# mattduino_leonardo.net
KiCad netlist of a schematic drawn in EAGLE
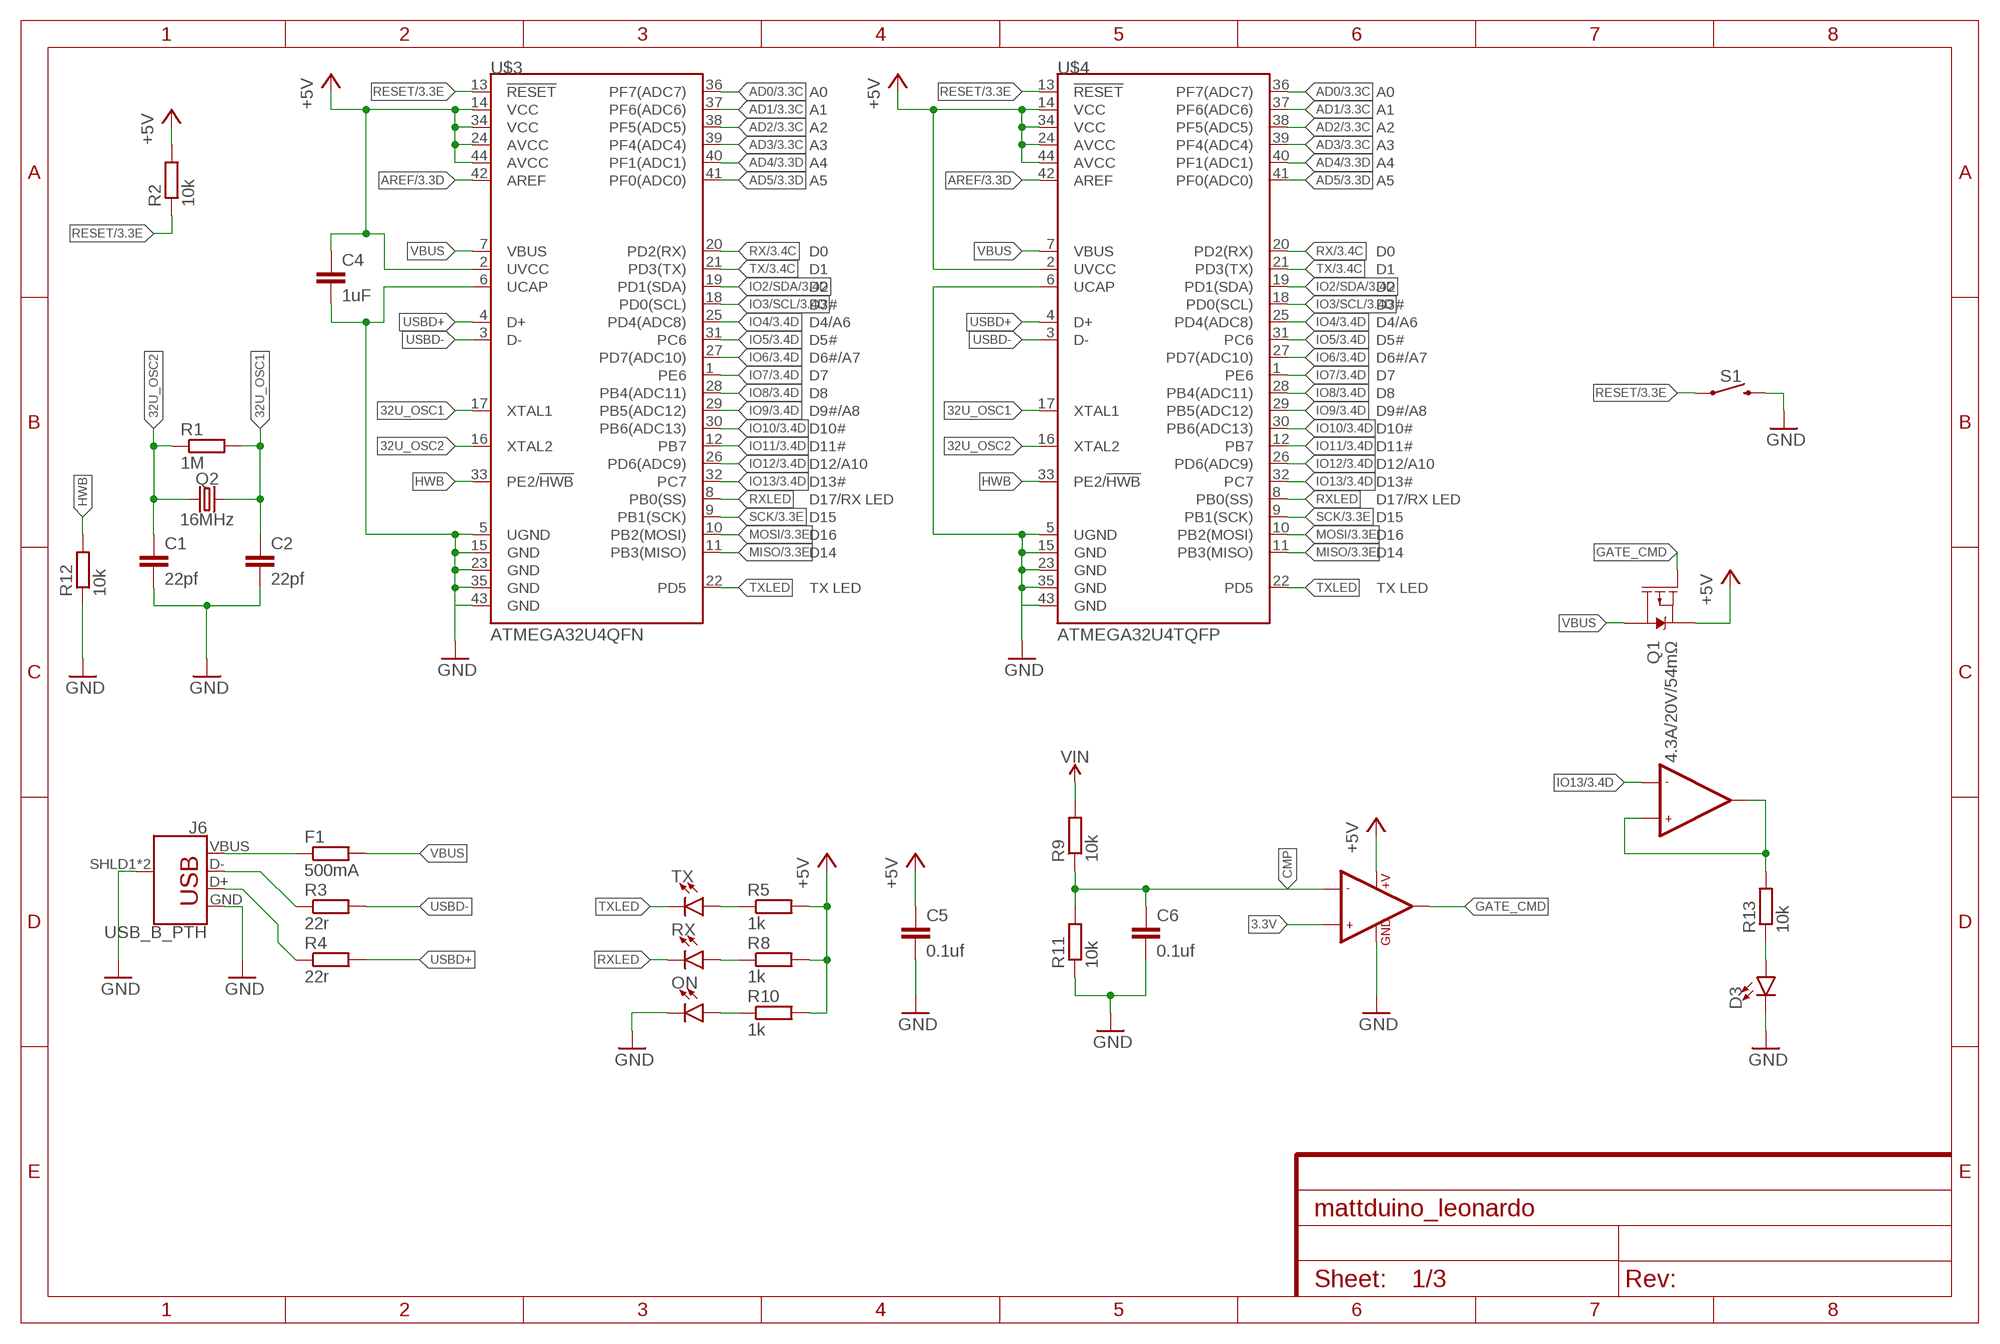
[diagram p0: schematic, sheet 1]
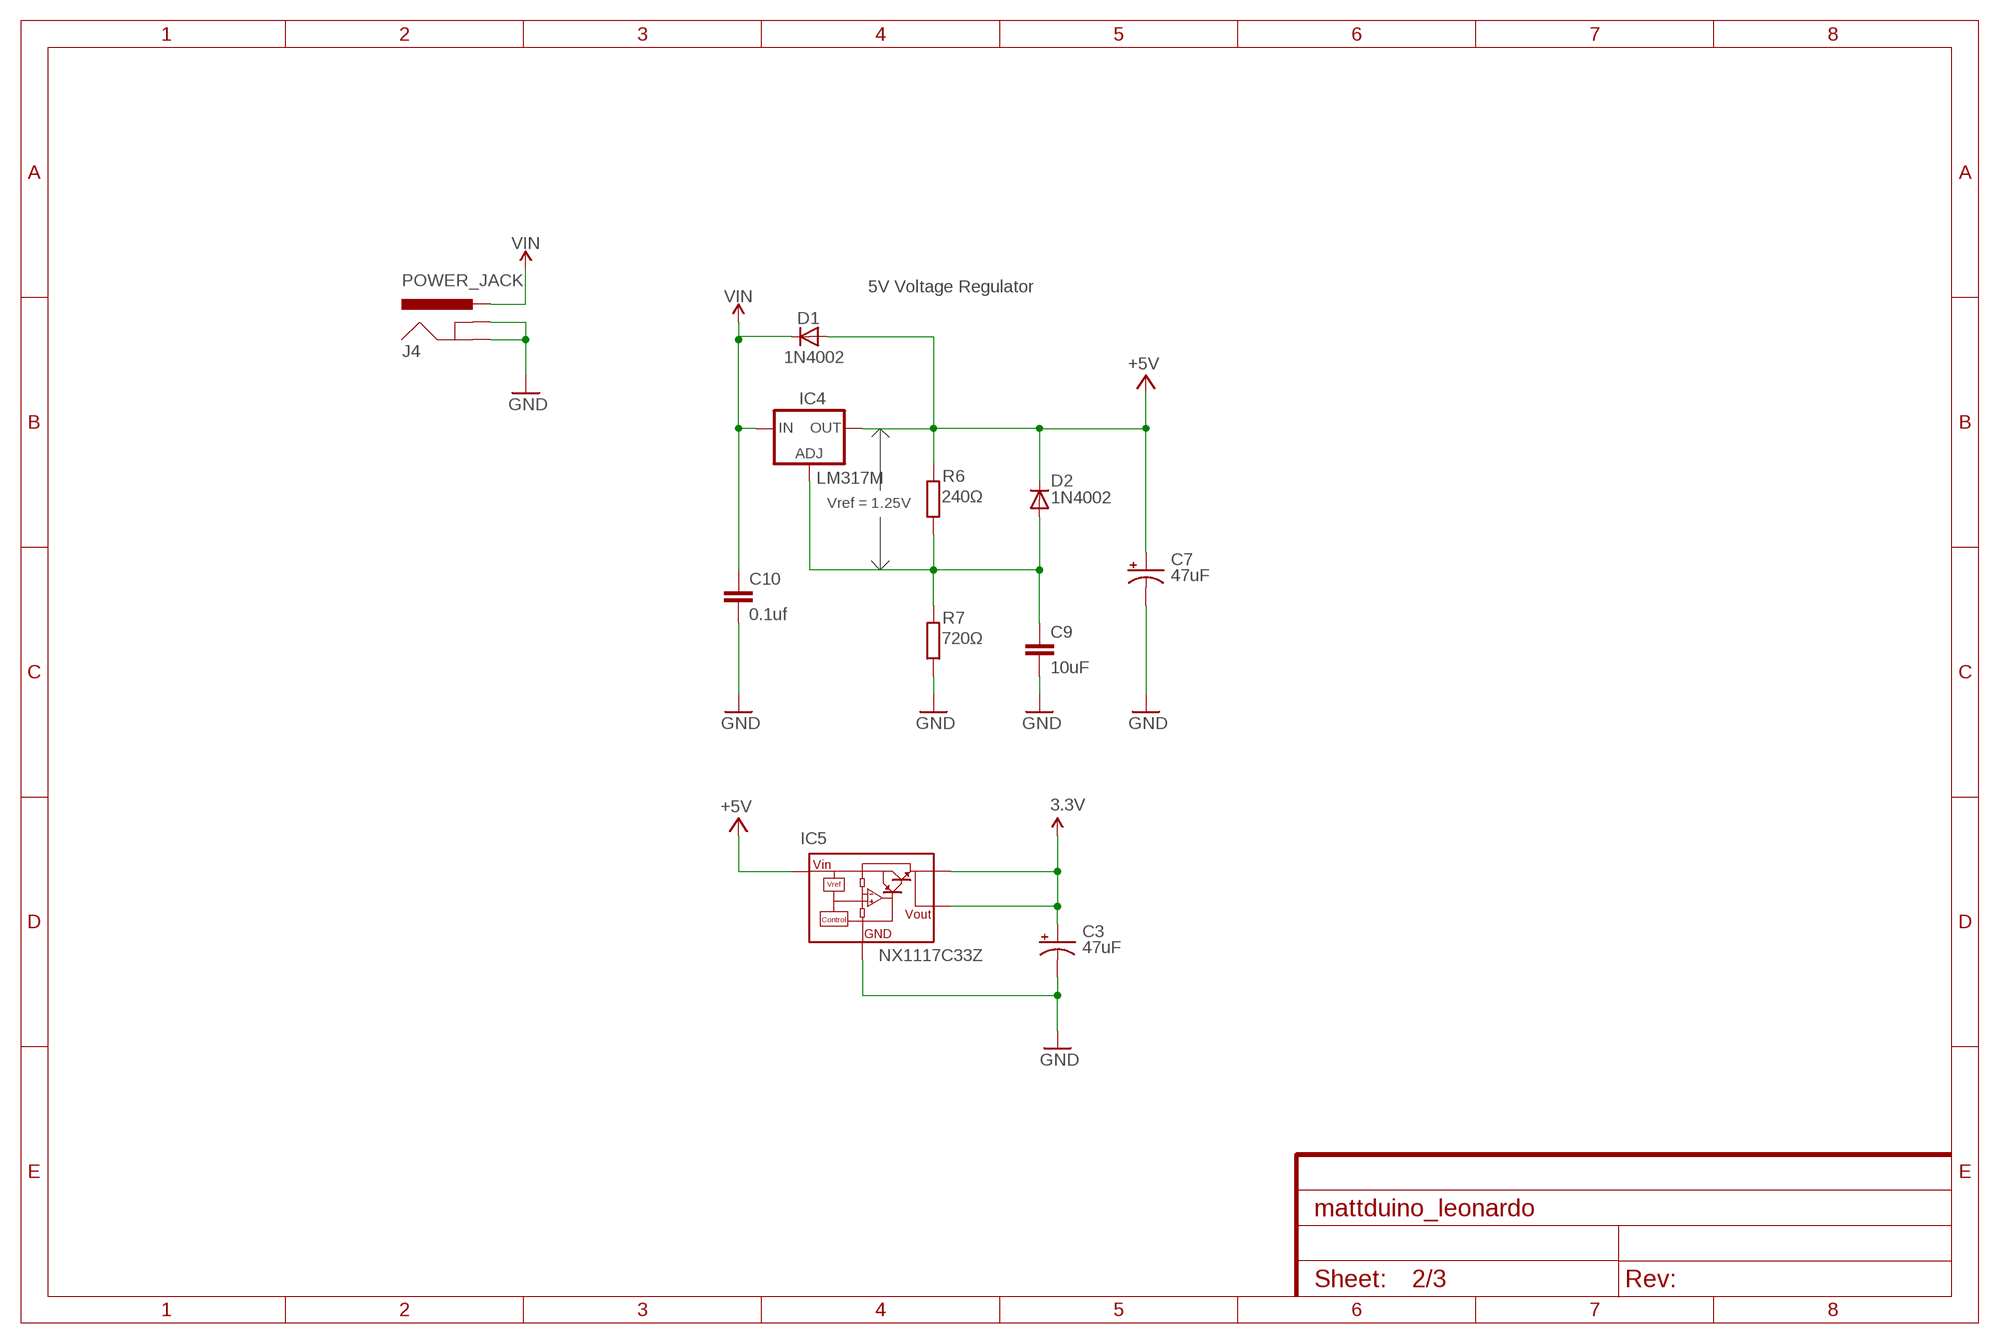
[diagram p1: schematic, sheet 2]
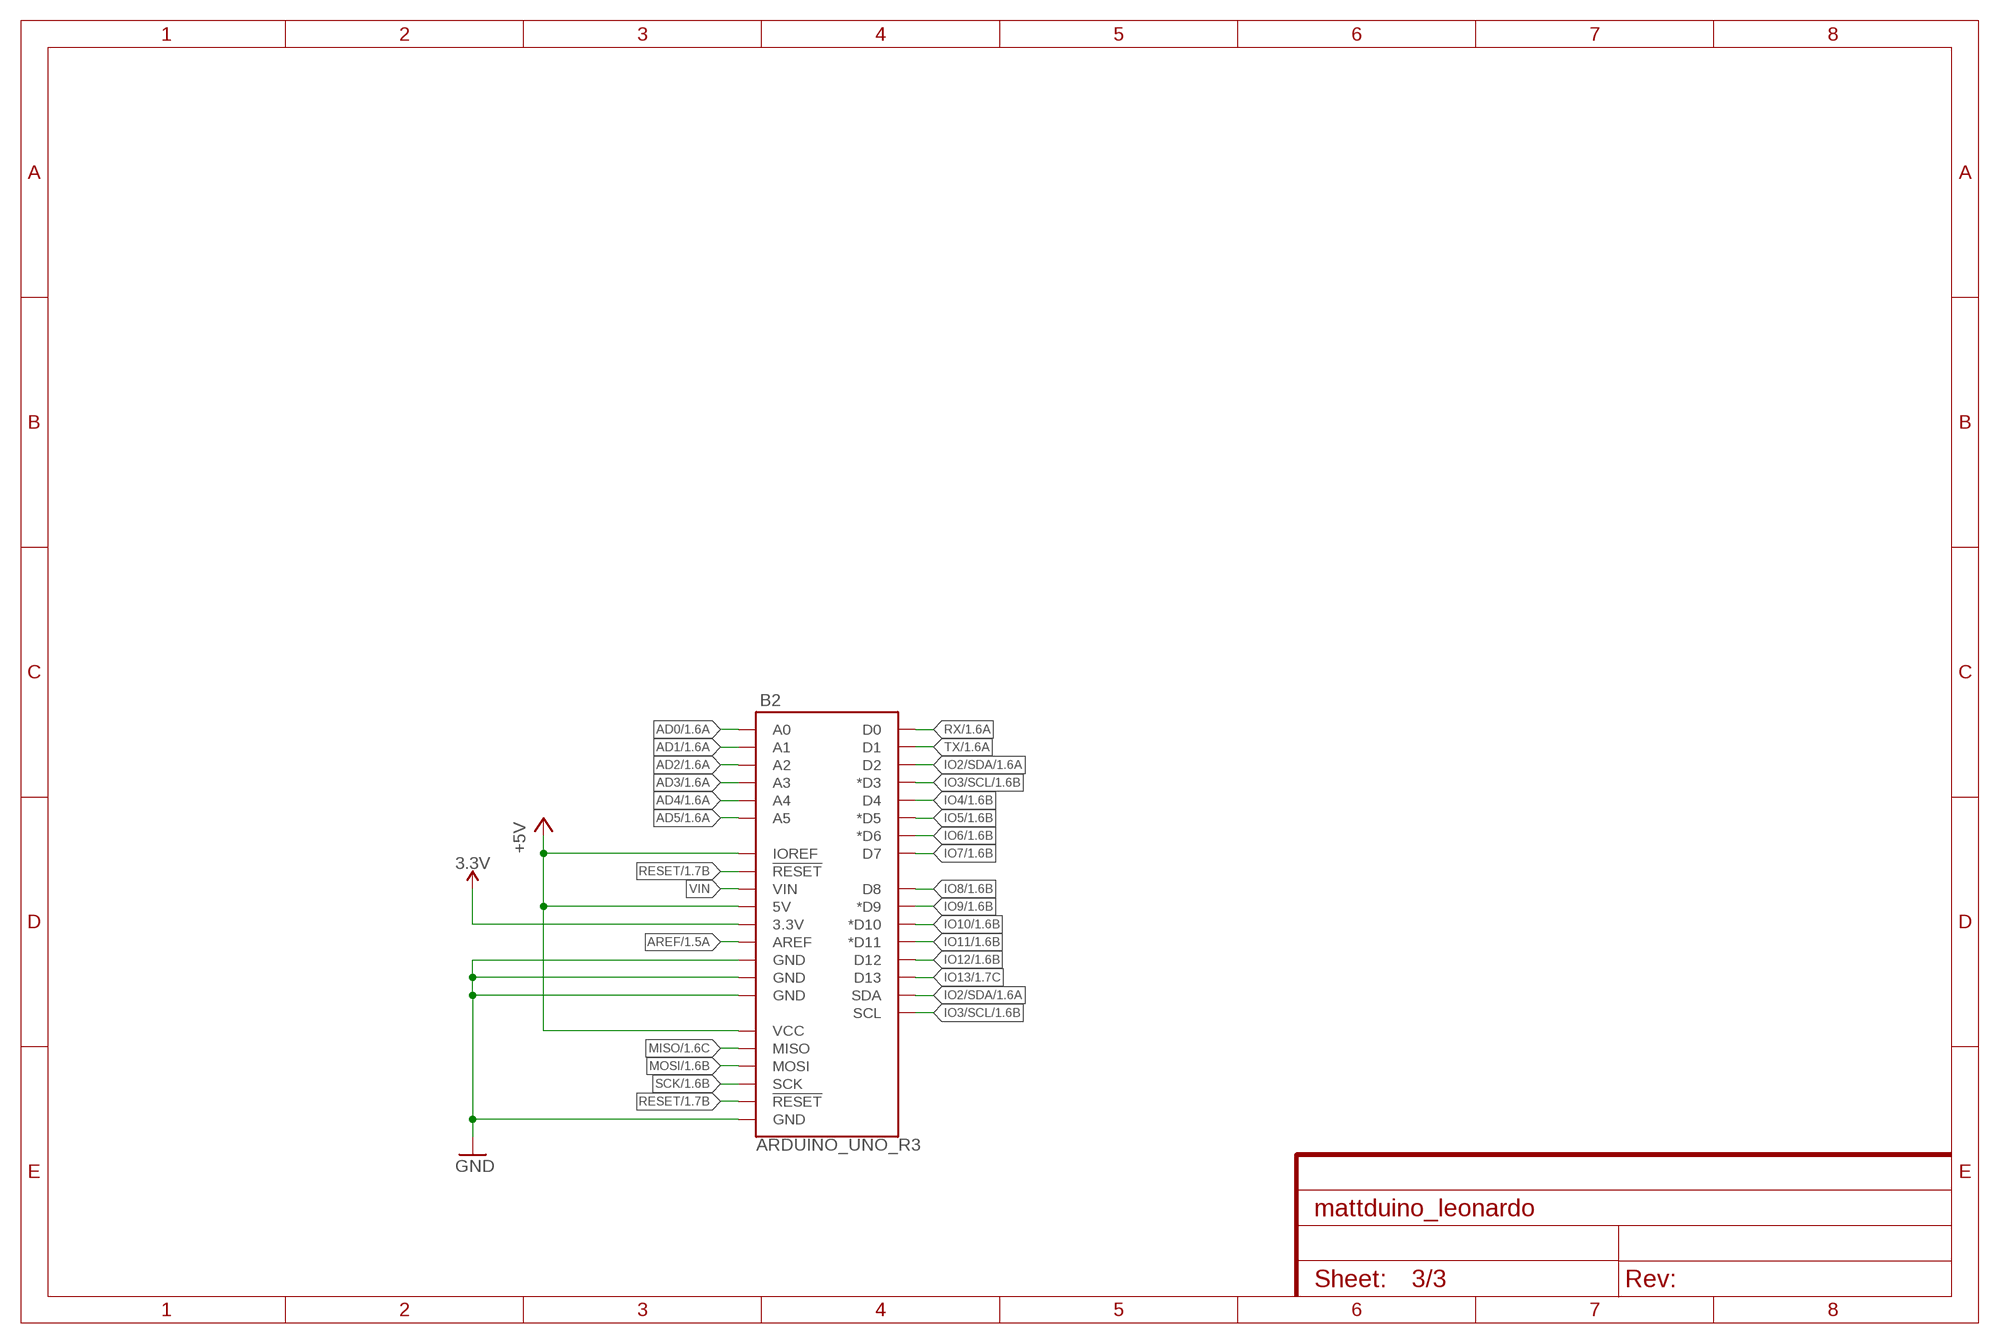
[diagram p2: schematic, sheet 3]

(export (version "E")
  (design (tool "Eeschema 10.0.6"))
  (components
    (comp (ref "C3")
      (value "47uF")
      (footprint "eagle-import:PANASONIC_D")
      (libsource (lib "eagle-import") (part "47UF-POLAR-PANASONIC_D-35V-20%"))
    )
    (comp (ref "C7")
      (value "47uF")
      (footprint "eagle-import:PANASONIC_D")
      (libsource (lib "eagle-import") (part "47UF-POLAR-PANASONIC_D-35V-20%"))
    )
    (comp (ref "C9")
      (value "10uF")
      (footprint "eagle-import:C1206")
      (libsource (lib "eagle-import") (part "C-EUC1206"))
    )
    (comp (ref "C10")
      (value "0.1uf")
      (footprint "eagle-import:C1206")
      (libsource (lib "eagle-import") (part "C-EUC1206"))
    )
    (comp (ref "D1")
      (value "1N4002")
      (footprint "eagle-import:SOD-123")
      (libsource (lib "eagle-import") (part "DIODESOD-123"))
    )
    (comp (ref "D2")
      (value "1N4002")
      (footprint "eagle-import:SOD-123")
      (libsource (lib "eagle-import") (part "DIODESOD-123"))
    )
    (comp (ref "IC4")
      (value "LM317MBSTT3")
      (footprint "eagle-import:SOT223")
      (fields (field (name "PARTNUMBER") "LM317M"))
      (libsource (lib "eagle-import") (part "LM317?MBSTT3"))
    )
    (comp (ref "IC5")
      (value "NX1117C33Z")
      (footprint "eagle-import:SOT223")
      (fields (field (name "TOLERANCE") "1.25%") (field (name "VOLTAGE") "5.0V"))
      (libsource (lib "eagle-import") (part "NX1117CZ33"))
    )
    (comp (ref "J4")
      (value "POWER_JACK")
      (footprint "eagle-import:POWER_JACK_PTH")
      (libsource (lib "eagle-import") (part "POWER_JACK"))
    )
    (comp (ref "R6")
      (value "240Ω")
      (footprint "eagle-import:R1206")
      (libsource (lib "eagle-import") (part "R-EU_R1206"))
    )
    (comp (ref "R7")
      (value "720Ω")
      (footprint "eagle-import:R1206")
      (libsource (lib "eagle-import") (part "R-EU_R1206"))
    )
    (comp (ref "B2")
      (value "ARDUINO_UNO_R3")
      (footprint "eagle-import:ARDUINO_R3")
      (libsource (lib "eagle-import") (part "ARDUINO_UNO_R3"))
    )
    (comp (ref "C1")
      (value "22pf")
      (footprint "eagle-import:C1206")
      (libsource (lib "eagle-import") (part "C-EUC1206"))
    )
    (comp (ref "C2")
      (value "22pf")
      (footprint "eagle-import:C1206")
      (libsource (lib "eagle-import") (part "C-EUC1206"))
    )
    (comp (ref "C4")
      (value "1uF")
      (footprint "eagle-import:C1206")
      (libsource (lib "eagle-import") (part "C-EUC1206"))
    )
    (comp (ref "C5")
      (value "0.1uf")
      (footprint "eagle-import:C1206")
      (libsource (lib "eagle-import") (part "C-EUC1206"))
    )
    (comp (ref "C6")
      (value "0.1uf")
      (footprint "eagle-import:C1206")
      (libsource (lib "eagle-import") (part "C-EUC1206"))
    )
    (comp (ref "D3")
      (value "LED1206")
      (footprint "eagle-import:LED-1206")
      (libsource (lib "eagle-import") (part "LED1206"))
    )
    (comp (ref "F1")
      (value "500mA")
      (footprint "eagle-import:R1206")
      (libsource (lib "eagle-import") (part "R-EU_R1206"))
    )
    (comp (ref "J6")
      (value "USB_B_PTH")
      (footprint "eagle-import:USB-B-PTH")
      (libsource (lib "eagle-import") (part "USB_B_PTH"))
    )
    (comp (ref "ON")
      (value "LED1206")
      (footprint "eagle-import:LED-1206")
      (libsource (lib "eagle-import") (part "LED1206"))
    )
    (comp (ref "Q1")
      (value "4.3A/20V/54mΩ")
      (footprint "eagle-import:SOT23-3")
      (libsource (lib "eagle-import") (part "MOSFET_PCH-IRLML2244"))
    )
    (comp (ref "Q2")
      (value "16MHz")
      (footprint "eagle-import:HC49UP")
      (libsource (lib "eagle-import") (part "CRYSTALSMD-HC49UP"))
    )
    (comp (ref "R1")
      (value "1M")
      (footprint "eagle-import:R1206")
      (libsource (lib "eagle-import") (part "R-EU_R1206"))
    )
    (comp (ref "R2")
      (value "10k")
      (footprint "eagle-import:R1206")
      (libsource (lib "eagle-import") (part "R-EU_R1206"))
    )
    (comp (ref "R3")
      (value "22r")
      (footprint "eagle-import:R1206")
      (libsource (lib "eagle-import") (part "R-EU_R1206"))
    )
    (comp (ref "R4")
      (value "22r")
      (footprint "eagle-import:R1206")
      (libsource (lib "eagle-import") (part "R-EU_R1206"))
    )
    (comp (ref "R5")
      (value "1k")
      (footprint "eagle-import:R1206")
      (libsource (lib "eagle-import") (part "R-EU_R1206"))
    )
    (comp (ref "R8")
      (value "1k")
      (footprint "eagle-import:R1206")
      (libsource (lib "eagle-import") (part "R-EU_R1206"))
    )
    (comp (ref "R9")
      (value "10k")
      (footprint "eagle-import:R1206")
      (libsource (lib "eagle-import") (part "R-EU_R1206"))
    )
    (comp (ref "R10")
      (value "1k")
      (footprint "eagle-import:R1206")
      (libsource (lib "eagle-import") (part "R-EU_R1206"))
    )
    (comp (ref "R11")
      (value "10k")
      (footprint "eagle-import:R1206")
      (libsource (lib "eagle-import") (part "R-EU_R1206"))
    )
    (comp (ref "R12")
      (value "10k")
      (footprint "eagle-import:R1206")
      (libsource (lib "eagle-import") (part "R-EU_R1206"))
    )
    (comp (ref "R13")
      (value "10k")
      (footprint "eagle-import:R1206")
      (libsource (lib "eagle-import") (part "R-EU_R1206"))
    )
    (comp (ref "RX")
      (value "LED1206")
      (footprint "eagle-import:LED-1206")
      (libsource (lib "eagle-import") (part "LED1206"))
    )
    (comp (ref "S1")
      (value "MOMENTARY-SWITCH-SPST-PTH-6.0MM-KIT")
      (footprint "eagle-import:TACTILE_SWITCH_PTH_6.0MM_KIT")
      (libsource (lib "eagle-import") (part "MOMENTARY-SWITCH-SPST-PTH-6.0MM-KIT"))
    )
    (comp (ref "TX")
      (value "LED1206")
      (footprint "eagle-import:LED-1206")
      (libsource (lib "eagle-import") (part "LED1206"))
    )
    (comp (ref "U$1")
      (value "LMV358")
      (footprint "eagle-import:SO08")
      (libsource (lib "eagle-import") (part "LMV358"))
    )
    (comp (ref "U$3")
      (value "ATMEGA32U4QFN")
      (footprint "eagle-import:SPARKFUN-DIGITALIC_QFN-44")
      (libsource (lib "eagle-import") (part "ATMEGA32U4QFN"))
    )
    (comp (ref "U$4")
      (value "ATMEGA32U4TQFP")
      (footprint "eagle-import:SPARKFUN-DIGITALIC_TQFP44")
      (libsource (lib "eagle-import") (part "ATMEGA32U4TQFP"))
    )
  )
  (nets
    (net (code "1") (name "+5V") (class "Default")
      (node (ref "B2") (pin "5V") (pinfunction "5V_5V") (pintype "bidirectional"))
      (node (ref "B2") (pin "IOREF") (pinfunction "IOREF_IOREF") (pintype "bidirectional"))
      (node (ref "B2") (pin "VCC") (pinfunction "VCC_VCC") (pintype "bidirectional"))
      (node (ref "C4") (pin "1") (pinfunction "1_1") (pintype "passive"))
      (node (ref "C5") (pin "1") (pinfunction "1_1") (pintype "passive"))
      (node (ref "C7") (pin "+") (pinfunction "+_+") (pintype "passive"))
      (node (ref "D1") (pin "A") (pinfunction "A_A") (pintype "passive"))
      (node (ref "D2") (pin "C") (pinfunction "C_C") (pintype "passive"))
      (node (ref "IC4") (pin "4") (pinfunction "OUT_4") (pintype "passive"))
      (node (ref "IC5") (pin "3") (pinfunction "VIN_3") (pintype "input"))
      (node (ref "Q1") (pin "2") (pinfunction "S_2") (pintype "bidirectional"))
      (node (ref "R10") (pin "2") (pinfunction "2_2") (pintype "passive"))
      (node (ref "R2") (pin "2") (pinfunction "2_2") (pintype "passive"))
      (node (ref "R5") (pin "2") (pinfunction "2_2") (pintype "passive"))
      (node (ref "R6") (pin "2") (pinfunction "2_2") (pintype "passive"))
      (node (ref "R8") (pin "2") (pinfunction "2_2") (pintype "passive"))
      (node (ref "U$1") (pin "8") (pinfunction "+V_8") (pintype "power_in"))
      (node (ref "U$3") (pin "14") (pinfunction "VCC_14") (pintype "bidirectional"))
      (node (ref "U$3") (pin "2") (pinfunction "UVCC_2") (pintype "bidirectional"))
      (node (ref "U$3") (pin "24") (pinfunction "AVCC_24") (pintype "bidirectional"))
      (node (ref "U$3") (pin "34") (pinfunction "VCC_34") (pintype "bidirectional"))
      (node (ref "U$3") (pin "44") (pinfunction "AVCC_44") (pintype "bidirectional"))
      (node (ref "U$4") (pin "14") (pinfunction "VCC_14") (pintype "bidirectional"))
      (node (ref "U$4") (pin "2") (pinfunction "UVCC_2") (pintype "bidirectional"))
      (node (ref "U$4") (pin "24") (pinfunction "AVCC_24") (pintype "bidirectional"))
      (node (ref "U$4") (pin "34") (pinfunction "VCC_34") (pintype "bidirectional"))
      (node (ref "U$4") (pin "44") (pinfunction "AVCC_44") (pintype "bidirectional"))
    )
    (net (code "2") (name "3.3V") (class "Default")
      (node (ref "B2") (pin "3.3V") (pinfunction "3.3V_3.3V") (pintype "bidirectional"))
      (node (ref "C3") (pin "+") (pinfunction "+_+") (pintype "passive"))
      (node (ref "IC5") (pin "2") (pinfunction "VOUT1_2") (pintype "output"))
      (node (ref "IC5") (pin "4") (pinfunction "VOUT_4") (pintype "output"))
      (node (ref "U$1") (pin "3") (pinfunction "+IN1_3") (pintype "input"))
    )
    (net (code "3") (name "32U_OSC1") (class "Default")
      (node (ref "C2") (pin "1") (pinfunction "1_1") (pintype "passive"))
      (node (ref "Q2") (pin "2") (pinfunction "2_2") (pintype "passive"))
      (node (ref "R1") (pin "2") (pinfunction "2_2") (pintype "passive"))
      (node (ref "U$3") (pin "17") (pinfunction "XTAL1_17") (pintype "bidirectional"))
      (node (ref "U$4") (pin "17") (pinfunction "XTAL1_17") (pintype "bidirectional"))
    )
    (net (code "4") (name "32U_OSC2") (class "Default")
      (node (ref "C1") (pin "1") (pinfunction "1_1") (pintype "passive"))
      (node (ref "Q2") (pin "1") (pinfunction "1_1") (pintype "passive"))
      (node (ref "R1") (pin "1") (pinfunction "1_1") (pintype "passive"))
      (node (ref "U$3") (pin "16") (pinfunction "XTAL2_16") (pintype "bidirectional"))
      (node (ref "U$4") (pin "16") (pinfunction "XTAL2_16") (pintype "bidirectional"))
    )
    (net (code "5") (name "AD0") (class "Default")
      (node (ref "B2") (pin "A0") (pinfunction "A0_A0") (pintype "bidirectional"))
      (node (ref "U$3") (pin "36") (pinfunction "PF7(ADC7)_36") (pintype "bidirectional"))
      (node (ref "U$4") (pin "36") (pinfunction "PF7(ADC7)_36") (pintype "bidirectional"))
    )
    (net (code "6") (name "AD1") (class "Default")
      (node (ref "B2") (pin "A1") (pinfunction "A1_A1") (pintype "bidirectional"))
      (node (ref "U$3") (pin "37") (pinfunction "PF6(ADC6)_37") (pintype "bidirectional"))
      (node (ref "U$4") (pin "37") (pinfunction "PF6(ADC6)_37") (pintype "bidirectional"))
    )
    (net (code "7") (name "AD2") (class "Default")
      (node (ref "B2") (pin "A2") (pinfunction "A2_A2") (pintype "bidirectional"))
      (node (ref "U$3") (pin "38") (pinfunction "PF5(ADC5)_38") (pintype "bidirectional"))
      (node (ref "U$4") (pin "38") (pinfunction "PF5(ADC5)_38") (pintype "bidirectional"))
    )
    (net (code "8") (name "AD3") (class "Default")
      (node (ref "B2") (pin "A3") (pinfunction "A3_A3") (pintype "bidirectional"))
      (node (ref "U$3") (pin "39") (pinfunction "PF4(ADC4)_39") (pintype "bidirectional"))
      (node (ref "U$4") (pin "39") (pinfunction "PF4(ADC4)_39") (pintype "bidirectional"))
    )
    (net (code "9") (name "AD4") (class "Default")
      (node (ref "B2") (pin "A4") (pinfunction "A4_A4") (pintype "bidirectional"))
      (node (ref "U$3") (pin "40") (pinfunction "PF1(ADC1)_40") (pintype "bidirectional"))
      (node (ref "U$4") (pin "40") (pinfunction "PF1(ADC1)_40") (pintype "bidirectional"))
    )
    (net (code "10") (name "AD5") (class "Default")
      (node (ref "B2") (pin "A5") (pinfunction "A5_A5") (pintype "bidirectional"))
      (node (ref "U$3") (pin "41") (pinfunction "PF0(ADC0)_41") (pintype "bidirectional"))
      (node (ref "U$4") (pin "41") (pinfunction "PF0(ADC0)_41") (pintype "bidirectional"))
    )
    (net (code "11") (name "AREF") (class "Default")
      (node (ref "B2") (pin "AREF") (pinfunction "AREF_AREF") (pintype "bidirectional"))
      (node (ref "U$3") (pin "42") (pinfunction "AREF_42") (pintype "bidirectional"))
      (node (ref "U$4") (pin "42") (pinfunction "AREF_42") (pintype "bidirectional"))
    )
    (net (code "12") (name "CMP") (class "Default")
      (node (ref "C6") (pin "1") (pinfunction "1_1") (pintype "passive"))
      (node (ref "R11") (pin "2") (pinfunction "2_2") (pintype "passive"))
      (node (ref "R9") (pin "1") (pinfunction "1_1") (pintype "passive"))
      (node (ref "U$1") (pin "2") (pinfunction "-IN1_2") (pintype "input"))
    )
    (net (code "13") (name "GATE_CMD") (class "Default")
      (node (ref "Q1") (pin "1") (pinfunction "G_1") (pintype "bidirectional"))
      (node (ref "U$1") (pin "1") (pinfunction "OUT1_1") (pintype "output"))
    )
    (net (code "14") (name "GND") (class "Default")
      (node (ref "B2") (pin "GND@1") (pinfunction "GND_GND@1") (pintype "bidirectional"))
      (node (ref "B2") (pin "GND@2") (pinfunction "GND_GND@2") (pintype "bidirectional"))
      (node (ref "B2") (pin "GND@3") (pinfunction "GND_GND@3") (pintype "bidirectional"))
      (node (ref "B2") (pin "GND@4") (pinfunction "GND_GND@4") (pintype "bidirectional"))
      (node (ref "C1") (pin "2") (pinfunction "2_2") (pintype "passive"))
      (node (ref "C10") (pin "2") (pinfunction "2_2") (pintype "passive"))
      (node (ref "C2") (pin "2") (pinfunction "2_2") (pintype "passive"))
      (node (ref "C3") (pin "-") (pinfunction "-_-") (pintype "passive"))
      (node (ref "C4") (pin "2") (pinfunction "2_2") (pintype "passive"))
      (node (ref "C5") (pin "2") (pinfunction "2_2") (pintype "passive"))
      (node (ref "C6") (pin "2") (pinfunction "2_2") (pintype "passive"))
      (node (ref "C7") (pin "-") (pinfunction "-_-") (pintype "passive"))
      (node (ref "C9") (pin "2") (pinfunction "2_2") (pintype "passive"))
      (node (ref "D3") (pin "C") (pinfunction "C_C") (pintype "passive"))
      (node (ref "IC5") (pin "1") (pinfunction "GND_1") (pintype "passive"))
      (node (ref "J4") (pin "GND") (pinfunction "GND_GND") (pintype "bidirectional"))
      (node (ref "J4") (pin "GNDBREAK") (pinfunction "GNDBREAK_GNDBREAK") (pintype "bidirectional"))
      (node (ref "J6") (pin "GND") (pinfunction "GND_GND") (pintype "power_in"))
      (node (ref "J6") (pin "SHLD1") (pinfunction "SHIELD_SHLD1") (pintype "bidirectional"))
      (node (ref "J6") (pin "SHLD2") (pinfunction "SHIELD_SHLD2") (pintype "bidirectional"))
      (node (ref "ON") (pin "C") (pinfunction "C_C") (pintype "passive"))
      (node (ref "R11") (pin "1") (pinfunction "1_1") (pintype "passive"))
      (node (ref "R12") (pin "1") (pinfunction "1_1") (pintype "passive"))
      (node (ref "R7") (pin "1") (pinfunction "1_1") (pintype "passive"))
      (node (ref "S1") (pin "3") (pinfunction "2_3") (pintype "passive"))
      (node (ref "U$1") (pin "4") (pinfunction "GND_4") (pintype "power_in"))
      (node (ref "U$3") (pin "15") (pinfunction "GND_15") (pintype "bidirectional"))
      (node (ref "U$3") (pin "23") (pinfunction "GND_23") (pintype "bidirectional"))
      (node (ref "U$3") (pin "35") (pinfunction "GND_35") (pintype "bidirectional"))
      (node (ref "U$3") (pin "43") (pinfunction "GND_43") (pintype "bidirectional"))
      (node (ref "U$3") (pin "5") (pinfunction "UGND_5") (pintype "bidirectional"))
      (node (ref "U$3") (pin "6") (pinfunction "UCAP_6") (pintype "bidirectional"))
      (node (ref "U$4") (pin "15") (pinfunction "GND_15") (pintype "bidirectional"))
      (node (ref "U$4") (pin "23") (pinfunction "GND_23") (pintype "bidirectional"))
      (node (ref "U$4") (pin "35") (pinfunction "GND_35") (pintype "bidirectional"))
      (node (ref "U$4") (pin "43") (pinfunction "GND_43") (pintype "bidirectional"))
      (node (ref "U$4") (pin "5") (pinfunction "UGND_5") (pintype "bidirectional"))
      (node (ref "U$4") (pin "6") (pinfunction "UCAP_6") (pintype "bidirectional"))
    )
    (net (code "15") (name "HWB") (class "Default")
      (node (ref "R12") (pin "2") (pinfunction "2_2") (pintype "passive"))
      (node (ref "U$3") (pin "33") (pinfunction "PE2/~{HWB}_33") (pintype "bidirectional"))
      (node (ref "U$4") (pin "33") (pinfunction "PE2/~{HWB}_33") (pintype "bidirectional"))
    )
    (net (code "16") (name "IO2{slash}SDA") (class "Default")
      (node (ref "B2") (pin "D2") (pinfunction "D2_D2") (pintype "bidirectional"))
      (node (ref "B2") (pin "SDA") (pinfunction "SDA_SDA") (pintype "bidirectional"))
      (node (ref "U$3") (pin "19") (pinfunction "PD1(SDA)_19") (pintype "bidirectional"))
      (node (ref "U$4") (pin "19") (pinfunction "PD1(SDA)_19") (pintype "bidirectional"))
    )
    (net (code "17") (name "IO3{slash}SCL") (class "Default")
      (node (ref "B2") (pin "D3") (pinfunction "*D3_D3") (pintype "bidirectional"))
      (node (ref "B2") (pin "SCL") (pinfunction "SCL_SCL") (pintype "bidirectional"))
      (node (ref "U$3") (pin "18") (pinfunction "PD0(SCL)_18") (pintype "bidirectional"))
      (node (ref "U$4") (pin "18") (pinfunction "PD0(SCL)_18") (pintype "bidirectional"))
    )
    (net (code "18") (name "IO4") (class "Default")
      (node (ref "B2") (pin "D4") (pinfunction "D4_D4") (pintype "bidirectional"))
      (node (ref "U$3") (pin "25") (pinfunction "PD4(ADC8)_25") (pintype "bidirectional"))
      (node (ref "U$4") (pin "25") (pinfunction "PD4(ADC8)_25") (pintype "bidirectional"))
    )
    (net (code "19") (name "IO5") (class "Default")
      (node (ref "B2") (pin "D5") (pinfunction "*D5_D5") (pintype "bidirectional"))
      (node (ref "U$3") (pin "31") (pinfunction "PC6_31") (pintype "bidirectional"))
      (node (ref "U$4") (pin "31") (pinfunction "PC6_31") (pintype "bidirectional"))
    )
    (net (code "20") (name "IO6") (class "Default")
      (node (ref "B2") (pin "D6") (pinfunction "*D6_D6") (pintype "bidirectional"))
      (node (ref "U$3") (pin "27") (pinfunction "PD7(ADC10)_27") (pintype "bidirectional"))
      (node (ref "U$4") (pin "27") (pinfunction "PD7(ADC10)_27") (pintype "bidirectional"))
    )
    (net (code "21") (name "IO7") (class "Default")
      (node (ref "B2") (pin "D7") (pinfunction "D7_D7") (pintype "bidirectional"))
      (node (ref "U$3") (pin "1") (pinfunction "PE6_1") (pintype "bidirectional"))
      (node (ref "U$4") (pin "1") (pinfunction "PE6_1") (pintype "bidirectional"))
    )
    (net (code "22") (name "IO8") (class "Default")
      (node (ref "B2") (pin "D8") (pinfunction "D8_D8") (pintype "bidirectional"))
      (node (ref "U$3") (pin "28") (pinfunction "PB4(ADC11)_28") (pintype "bidirectional"))
      (node (ref "U$4") (pin "28") (pinfunction "PB4(ADC11)_28") (pintype "bidirectional"))
    )
    (net (code "23") (name "IO9") (class "Default")
      (node (ref "B2") (pin "D9") (pinfunction "*D9_D9") (pintype "bidirectional"))
      (node (ref "U$3") (pin "29") (pinfunction "PB5(ADC12)_29") (pintype "bidirectional"))
      (node (ref "U$4") (pin "29") (pinfunction "PB5(ADC12)_29") (pintype "bidirectional"))
    )
    (net (code "24") (name "IO10") (class "Default")
      (node (ref "B2") (pin "D10") (pinfunction "*D10_D10") (pintype "bidirectional"))
      (node (ref "U$3") (pin "30") (pinfunction "PB6(ADC13)_30") (pintype "bidirectional"))
      (node (ref "U$4") (pin "30") (pinfunction "PB6(ADC13)_30") (pintype "bidirectional"))
    )
    (net (code "25") (name "IO11") (class "Default")
      (node (ref "B2") (pin "D11") (pinfunction "*D11_D11") (pintype "bidirectional"))
      (node (ref "U$3") (pin "12") (pinfunction "PB7_12") (pintype "bidirectional"))
      (node (ref "U$4") (pin "12") (pinfunction "PB7_12") (pintype "bidirectional"))
    )
    (net (code "26") (name "IO12") (class "Default")
      (node (ref "B2") (pin "D12") (pinfunction "D12_D12") (pintype "bidirectional"))
      (node (ref "U$3") (pin "26") (pinfunction "PD6(ADC9)_26") (pintype "bidirectional"))
      (node (ref "U$4") (pin "26") (pinfunction "PD6(ADC9)_26") (pintype "bidirectional"))
    )
    (net (code "27") (name "IO13") (class "Default")
      (node (ref "B2") (pin "D13") (pinfunction "D13_D13") (pintype "bidirectional"))
      (node (ref "U$1") (pin "6") (pinfunction "-IN2_6") (pintype "input"))
      (node (ref "U$3") (pin "32") (pinfunction "PC7_32") (pintype "bidirectional"))
      (node (ref "U$4") (pin "32") (pinfunction "PC7_32") (pintype "bidirectional"))
    )
    (net (code "28") (name "MISO") (class "Default")
      (node (ref "B2") (pin "MISO") (pinfunction "MISO_MISO") (pintype "bidirectional"))
      (node (ref "U$3") (pin "11") (pinfunction "PB3(MISO)_11") (pintype "bidirectional"))
      (node (ref "U$4") (pin "11") (pinfunction "PB3(MISO)_11") (pintype "bidirectional"))
    )
    (net (code "29") (name "MOSI") (class "Default")
      (node (ref "B2") (pin "MOSI") (pinfunction "MOSI_MOSI") (pintype "bidirectional"))
      (node (ref "U$3") (pin "10") (pinfunction "PB2(MOSI)_10") (pintype "bidirectional"))
      (node (ref "U$4") (pin "10") (pinfunction "PB2(MOSI)_10") (pintype "bidirectional"))
    )
    (net (code "30") (name "Net-(D3-PadA)") (class "Default")
      (node (ref "D3") (pin "A") (pinfunction "A_A") (pintype "passive"))
      (node (ref "R13") (pin "1") (pinfunction "1_1") (pintype "passive"))
    )
    (net (code "31") (name "Net-(F1-Pad1)") (class "Default")
      (node (ref "F1") (pin "1") (pinfunction "1_1") (pintype "passive"))
      (node (ref "J6") (pin "VBUS") (pinfunction "VBUS_VBUS") (pintype "power_in"))
    )
    (net (code "32") (name "Net-(IC4-ADJ)") (class "Default")
      (node (ref "C9") (pin "1") (pinfunction "1_1") (pintype "passive"))
      (node (ref "D2") (pin "A") (pinfunction "A_A") (pintype "passive"))
      (node (ref "IC4") (pin "1") (pinfunction "ADJ_1") (pintype "input"))
      (node (ref "R6") (pin "1") (pinfunction "1_1") (pintype "passive"))
      (node (ref "R7") (pin "2") (pinfunction "2_2") (pintype "passive"))
    )
    (net (code "33") (name "Net-(J6-PadD+)") (class "Default")
      (node (ref "J6") (pin "D+") (pinfunction "D+_D+") (pintype "bidirectional"))
      (node (ref "R4") (pin "1") (pinfunction "1_1") (pintype "passive"))
    )
    (net (code "34") (name "Net-(J6-PadD-)") (class "Default")
      (node (ref "J6") (pin "D-") (pinfunction "D-_D-") (pintype "bidirectional"))
      (node (ref "R3") (pin "1") (pinfunction "1_1") (pintype "passive"))
    )
    (net (code "35") (name "Net-(ON-PadA)") (class "Default")
      (node (ref "ON") (pin "A") (pinfunction "A_A") (pintype "passive"))
      (node (ref "R10") (pin "1") (pinfunction "1_1") (pintype "passive"))
    )
    (net (code "36") (name "Net-(R5-Pad1)") (class "Default")
      (node (ref "R5") (pin "1") (pinfunction "1_1") (pintype "passive"))
      (node (ref "TX") (pin "A") (pinfunction "A_A") (pintype "passive"))
    )
    (net (code "37") (name "Net-(R8-Pad1)") (class "Default")
      (node (ref "R8") (pin "1") (pinfunction "1_1") (pintype "passive"))
      (node (ref "RX") (pin "A") (pinfunction "A_A") (pintype "passive"))
    )
    (net (code "38") (name "Net-(U$1B-+IN2)") (class "Default")
      (node (ref "R13") (pin "2") (pinfunction "2_2") (pintype "passive"))
      (node (ref "U$1") (pin "5") (pinfunction "+IN2_5") (pintype "input"))
      (node (ref "U$1") (pin "7") (pinfunction "OUT2_7") (pintype "output"))
    )
    (net (code "39") (name "RESET") (class "Default")
      (node (ref "B2") (pin "RESET@1") (pinfunction "~{RESET}_RESET@1") (pintype "bidirectional"))
      (node (ref "B2") (pin "RESET@2") (pinfunction "~{RESET}_RESET@2") (pintype "bidirectional"))
      (node (ref "R2") (pin "1") (pinfunction "1_1") (pintype "passive"))
      (node (ref "S1") (pin "1") (pinfunction "1_1") (pintype "passive"))
      (node (ref "U$3") (pin "13") (pinfunction "~{RESET}_13") (pintype "bidirectional"))
      (node (ref "U$4") (pin "13") (pinfunction "~{RESET}_13") (pintype "bidirectional"))
    )
    (net (code "40") (name "RX") (class "Default")
      (node (ref "B2") (pin "D0") (pinfunction "D0_D0") (pintype "bidirectional"))
      (node (ref "U$3") (pin "20") (pinfunction "PD2(RX)_20") (pintype "bidirectional"))
      (node (ref "U$4") (pin "20") (pinfunction "PD2(RX)_20") (pintype "bidirectional"))
    )
    (net (code "41") (name "RXLED") (class "Default")
      (node (ref "RX") (pin "C") (pinfunction "C_C") (pintype "passive"))
      (node (ref "U$3") (pin "8") (pinfunction "PB0(SS)_8") (pintype "bidirectional"))
      (node (ref "U$4") (pin "8") (pinfunction "PB0(SS)_8") (pintype "bidirectional"))
    )
    (net (code "42") (name "SCK") (class "Default")
      (node (ref "B2") (pin "SCK") (pinfunction "SCK_SCK") (pintype "bidirectional"))
      (node (ref "U$3") (pin "9") (pinfunction "PB1(SCK)_9") (pintype "bidirectional"))
      (node (ref "U$4") (pin "9") (pinfunction "PB1(SCK)_9") (pintype "bidirectional"))
    )
    (net (code "43") (name "TX") (class "Default")
      (node (ref "B2") (pin "D1") (pinfunction "D1_D1") (pintype "bidirectional"))
      (node (ref "U$3") (pin "21") (pinfunction "PD3(TX)_21") (pintype "bidirectional"))
      (node (ref "U$4") (pin "21") (pinfunction "PD3(TX)_21") (pintype "bidirectional"))
    )
    (net (code "44") (name "TXLED") (class "Default")
      (node (ref "TX") (pin "C") (pinfunction "C_C") (pintype "passive"))
      (node (ref "U$3") (pin "22") (pinfunction "PD5_22") (pintype "bidirectional"))
      (node (ref "U$4") (pin "22") (pinfunction "PD5_22") (pintype "bidirectional"))
    )
    (net (code "45") (name "USBD+") (class "Default")
      (node (ref "R4") (pin "2") (pinfunction "2_2") (pintype "passive"))
      (node (ref "U$3") (pin "4") (pinfunction "D+_4") (pintype "bidirectional"))
      (node (ref "U$4") (pin "4") (pinfunction "D+_4") (pintype "bidirectional"))
    )
    (net (code "46") (name "USBD-") (class "Default")
      (node (ref "R3") (pin "2") (pinfunction "2_2") (pintype "passive"))
      (node (ref "U$3") (pin "3") (pinfunction "D-_3") (pintype "bidirectional"))
      (node (ref "U$4") (pin "3") (pinfunction "D-_3") (pintype "bidirectional"))
    )
    (net (code "47") (name "VBUS") (class "Default")
      (node (ref "F1") (pin "2") (pinfunction "2_2") (pintype "passive"))
      (node (ref "Q1") (pin "3") (pinfunction "D_3") (pintype "bidirectional"))
      (node (ref "U$3") (pin "7") (pinfunction "VBUS_7") (pintype "bidirectional"))
      (node (ref "U$4") (pin "7") (pinfunction "VBUS_7") (pintype "bidirectional"))
    )
    (net (code "48") (name "VIN") (class "Default")
      (node (ref "B2") (pin "VIN") (pinfunction "VIN_VIN") (pintype "bidirectional"))
      (node (ref "C10") (pin "1") (pinfunction "1_1") (pintype "passive"))
      (node (ref "D1") (pin "C") (pinfunction "C_C") (pintype "passive"))
      (node (ref "IC4") (pin "3") (pinfunction "IN_3") (pintype "input"))
      (node (ref "J4") (pin "PWR") (pinfunction "PWR_PWR") (pintype "bidirectional"))
      (node (ref "R9") (pin "2") (pinfunction "2_2") (pintype "passive"))
    )
  )
)
